# RS485_Channel_1.net
KiCad netlist of a schematic drawn in Altium Designer
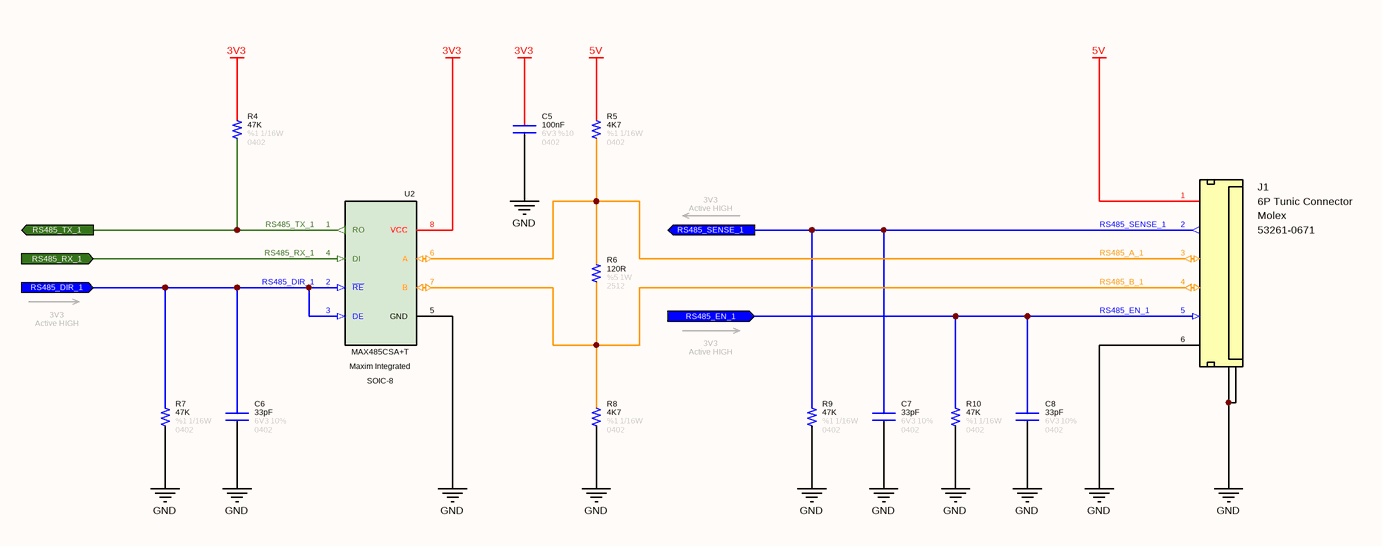
[diagram p0: RS485 Channel 1.SchDoc]

(export (version "E")
  (design (tool "Eeschema 10.0.6"))
  (components
    (comp (ref "C5")
      (value "100nF")
      (footprint "CAPACITOR_0402")
      (description "Capacitor - 100nF [0402-6V3] (Ceramic)")
      (fields
        (field (name "MANUFACTURER PART NUMBER") "04026D104KAT4A")
        (field (name "TOLERANCE") "%10")
        (field (name "VOLTAGE") "6V3")
        (field (name "CASE") "0402")
        (field (name "Comment") "Capacitor - 100nF [0402] (Ceramic)")
      )
      (libsource (lib "Akkoyun") (part "Capacitor - 100nF [0402-6V3]"))
    )
    (comp (ref "C6")
      (value "33pF")
      (footprint "CAPACITOR_0402")
      (description "Capacitor - 33pF [0402] (Ceramic)")
      (fields
        (field (name "MANUFACTURER PART NUMBER") "C0402C330J9RACAUTO")
        (field (name "TOLERANCE") "10%")
        (field (name "CASE") "0402")
        (field (name "VOLTAGE") "6V3")
      )
      (libsource (lib "Akkoyun") (part "Capacitor - 33pF [0402-6V3]"))
    )
    (comp (ref "C7")
      (value "33pF")
      (footprint "CAPACITOR_0402")
      (description "Capacitor - 33pF [0402] (Ceramic)")
      (fields
        (field (name "MANUFACTURER PART NUMBER") "C0402C330J9RACAUTO")
        (field (name "TOLERANCE") "10%")
        (field (name "CASE") "0402")
        (field (name "VOLTAGE") "6V3")
      )
      (libsource (lib "Akkoyun") (part "Capacitor - 33pF [0402-6V3]"))
    )
    (comp (ref "C8")
      (value "33pF")
      (footprint "CAPACITOR_0402")
      (description "Capacitor - 33pF [0402] (Ceramic)")
      (fields
        (field (name "MANUFACTURER PART NUMBER") "C0402C330J9RACAUTO")
        (field (name "TOLERANCE") "10%")
        (field (name "CASE") "0402")
        (field (name "VOLTAGE") "6V3")
      )
      (libsource (lib "Akkoyun") (part "Capacitor - 33pF [0402-6V3]"))
    )
    (comp (ref "J1")
      (value "6P Tunic Connector")
      (footprint "Connector_Tunic 6P")
      (description "Mini Tunic Connector with 6P")
      (fields
        (field (name "MANUFACTURER PART NUMBER") "53261-0671")
        (field (name "MANUFACTURER NAME") "Molex")
      )
      (libsource (lib "Akkoyun") (part "Connector - Mini Tunic 6P (1.25)"))
    )
    (comp (ref "R4")
      (value "47K")
      (footprint "RESISTOR_0402")
      (description "Thick Film Resistors - SMD 1/16 W 47 KOhm 1%")
      (fields
        (field (name "MANUFACTURER PART NUMBER") "CRCW040247K0FKED")
        (field (name "TOLERANCE") "%1")
        (field (name "CASE") "0402")
        (field (name "POWER") "1/16W")
        (field (name "Comment") "47K - 0402 - %1 - 1/16W")
      )
      (libsource (lib "Akkoyun") (part "Resistor - 47K [0402]"))
    )
    (comp (ref "R5")
      (value "4K7")
      (footprint "RESISTOR_0402")
      (description "Thick Film Resistors - SMD 1/16 W 4.7 KOhm 1%")
      (fields
        (field (name "MANUFACTURER PART NUMBER") "CRCW04024K70FKED")
        (field (name "TOLERANCE") "%1")
        (field (name "CASE") "0402")
        (field (name "POWER") "1/16W")
        (field (name "Comment") "4K7 - 0402 - %1 - 1/16W")
      )
      (libsource (lib "Akkoyun") (part "Resistor - 4K7 [0402]"))
    )
    (comp (ref "R6")
      (value "120R")
      (footprint "RESISTOR_2512")
      (description "Thick Film Resistors - SMD 1 W 120 Ohm 5%")
      (fields
        (field (name "MANUFACTURER PART NUMBER") "RC2512JK-07120RL")
        (field (name "TOLERANCE") "%5")
        (field (name "CASE") "2512")
        (field (name "POWER") "1W")
        (field (name "Comment") "120R - 2512 - %5 - 1W")
      )
      (libsource (lib "Akkoyun") (part "Resistor - 120R [2512]"))
    )
    (comp (ref "R7")
      (value "47K")
      (footprint "RESISTOR_0402")
      (description "Thick Film Resistors - SMD 1/16 W 47 KOhm 1%")
      (fields
        (field (name "MANUFACTURER PART NUMBER") "CRCW040247K0FKED")
        (field (name "TOLERANCE") "%1")
        (field (name "CASE") "0402")
        (field (name "POWER") "1/16W")
        (field (name "Comment") "47K - 0402 - %1 - 1/16W")
      )
      (libsource (lib "Akkoyun") (part "Resistor - 47K [0402]"))
    )
    (comp (ref "R8")
      (value "4K7")
      (footprint "RESISTOR_0402")
      (description "Thick Film Resistors - SMD 1/16 W 4.7 KOhm 1%")
      (fields
        (field (name "MANUFACTURER PART NUMBER") "CRCW04024K70FKED")
        (field (name "TOLERANCE") "%1")
        (field (name "CASE") "0402")
        (field (name "POWER") "1/16W")
        (field (name "Comment") "4K7 - 0402 - %1 - 1/16W")
      )
      (libsource (lib "Akkoyun") (part "Resistor - 4K7 [0402]"))
    )
    (comp (ref "R9")
      (value "47K")
      (footprint "RESISTOR_0402")
      (description "Thick Film Resistors - SMD 1/16 W 47 KOhm 1%")
      (fields
        (field (name "MANUFACTURER PART NUMBER") "CRCW040247K0FKED")
        (field (name "TOLERANCE") "%1")
        (field (name "CASE") "0402")
        (field (name "POWER") "1/16W")
        (field (name "Comment") "47K - 0402 - %1 - 1/16W")
      )
      (libsource (lib "Akkoyun") (part "Resistor - 47K [0402]"))
    )
    (comp (ref "R10")
      (value "47K")
      (footprint "RESISTOR_0402")
      (description "Thick Film Resistors - SMD 1/16 W 47 KOhm 1%")
      (fields
        (field (name "MANUFACTURER PART NUMBER") "CRCW040247K0FKED")
        (field (name "TOLERANCE") "%1")
        (field (name "CASE") "0402")
        (field (name "POWER") "1/16W")
        (field (name "Comment") "47K - 0402 - %1 - 1/16W")
      )
      (libsource (lib "Akkoyun") (part "Resistor - 47K [0402]"))
    )
    (comp (ref "U2")
      (value "RS485 Modulator")
      (footprint "SOP-8L (AZRS3080E)")
      (description "RS-422/RS-485 Interface IC Low-Power, Slew-Rate-Limited RS-485/RS-422 Transceivers")
      (fields
        (field (name "CASE") "SOIC-8")
        (field (name "MANUFACTURER PART NUMBER") "MAX485CSA+T")
        (field (name "MANUFACTURER NAME") "Maxim Integrated")
      )
      (libsource (lib "Akkoyun") (part "IC - MAX485CSA+T"))
    )
  )
  (nets
    (net (code "1") (name "/RS485_A_1") (class "Default")
      (node (ref "J1") (pin "3") (pinfunction "RS485-A_3") (pintype "bidirectional"))
      (node (ref "R5") (pin "1") (pinfunction "1_1") (pintype "passive"))
      (node (ref "R6") (pin "2") (pinfunction "2_2") (pintype "passive"))
      (node (ref "U2") (pin "6") (pinfunction "A_6") (pintype "bidirectional"))
    )
    (net (code "2") (name "/RS485_B_1") (class "Default")
      (node (ref "J1") (pin "4") (pinfunction "RS485-B_4") (pintype "bidirectional"))
      (node (ref "R6") (pin "1") (pinfunction "1_1") (pintype "passive"))
      (node (ref "R8") (pin "2") (pinfunction "2_2") (pintype "passive"))
      (node (ref "U2") (pin "7") (pinfunction "B_7") (pintype "bidirectional"))
    )
    (net (code "3") (name "/RS485_DIR_1") (class "Default")
      (node (ref "C6") (pin "2") (pinfunction "2_2") (pintype "passive"))
      (node (ref "R7") (pin "2") (pinfunction "2_2") (pintype "passive"))
      (node (ref "U2") (pin "2") (pinfunction "~{RE}_2") (pintype "input"))
      (node (ref "U2") (pin "3") (pinfunction "DE_3") (pintype "input"))
    )
    (net (code "4") (name "/RS485_EN_1") (class "Default")
      (node (ref "C8") (pin "2") (pinfunction "2_2") (pintype "passive"))
      (node (ref "J1") (pin "5") (pinfunction "INT_5") (pintype "input"))
      (node (ref "R10") (pin "2") (pinfunction "2_2") (pintype "passive"))
    )
    (net (code "5") (name "/RS485_RX_1") (class "Default")
      (node (ref "U2") (pin "4") (pinfunction "DI_4") (pintype "input"))
    )
    (net (code "6") (name "/RS485_SENSE_1") (class "Default")
      (node (ref "C7") (pin "2") (pinfunction "2_2") (pintype "passive"))
      (node (ref "J1") (pin "2") (pinfunction "Sense_2") (pintype "output"))
      (node (ref "R9") (pin "2") (pinfunction "2_2") (pintype "passive"))
    )
    (net (code "7") (name "/RS485_TX_1") (class "Default")
      (node (ref "R4") (pin "1") (pinfunction "1_1") (pintype "passive"))
      (node (ref "U2") (pin "1") (pinfunction "RO_1") (pintype "output"))
    )
    (net (code "8") (name "3V3") (class "Default")
      (node (ref "C5") (pin "2") (pinfunction "2_2") (pintype "passive"))
      (node (ref "R4") (pin "2") (pinfunction "2_2") (pintype "passive"))
      (node (ref "U2") (pin "8") (pinfunction "VCC_8") (pintype "power_in"))
    )
    (net (code "9") (name "5V") (class "Default")
      (node (ref "J1") (pin "1") (pinfunction "5V_1") (pintype "power_in"))
      (node (ref "R5") (pin "2") (pinfunction "2_2") (pintype "passive"))
    )
    (net (code "10") (name "GND") (class "Default")
      (node (ref "C5") (pin "1") (pinfunction "1_1") (pintype "passive"))
      (node (ref "C6") (pin "1") (pinfunction "1_1") (pintype "passive"))
      (node (ref "C7") (pin "1") (pinfunction "1_1") (pintype "passive"))
      (node (ref "C8") (pin "1") (pinfunction "1_1") (pintype "passive"))
      (node (ref "J1") (pin "6") (pinfunction "GND_6") (pintype "power_in"))
      (node (ref "J1") (pin "7") (pinfunction "GND_7") (pintype "passive"))
      (node (ref "J1") (pin "8") (pinfunction "GND_8") (pintype "passive"))
      (node (ref "R10") (pin "1") (pinfunction "1_1") (pintype "passive"))
      (node (ref "R7") (pin "1") (pinfunction "1_1") (pintype "passive"))
      (node (ref "R8") (pin "1") (pinfunction "1_1") (pintype "passive"))
      (node (ref "R9") (pin "1") (pinfunction "1_1") (pintype "passive"))
      (node (ref "U2") (pin "5") (pinfunction "GND_5") (pintype "passive"))
    )
  )
)
